# PCB-PAYLOAD-MIRRORED_FINAL.net
KiCad netlist of a schematic drawn in EAGLE
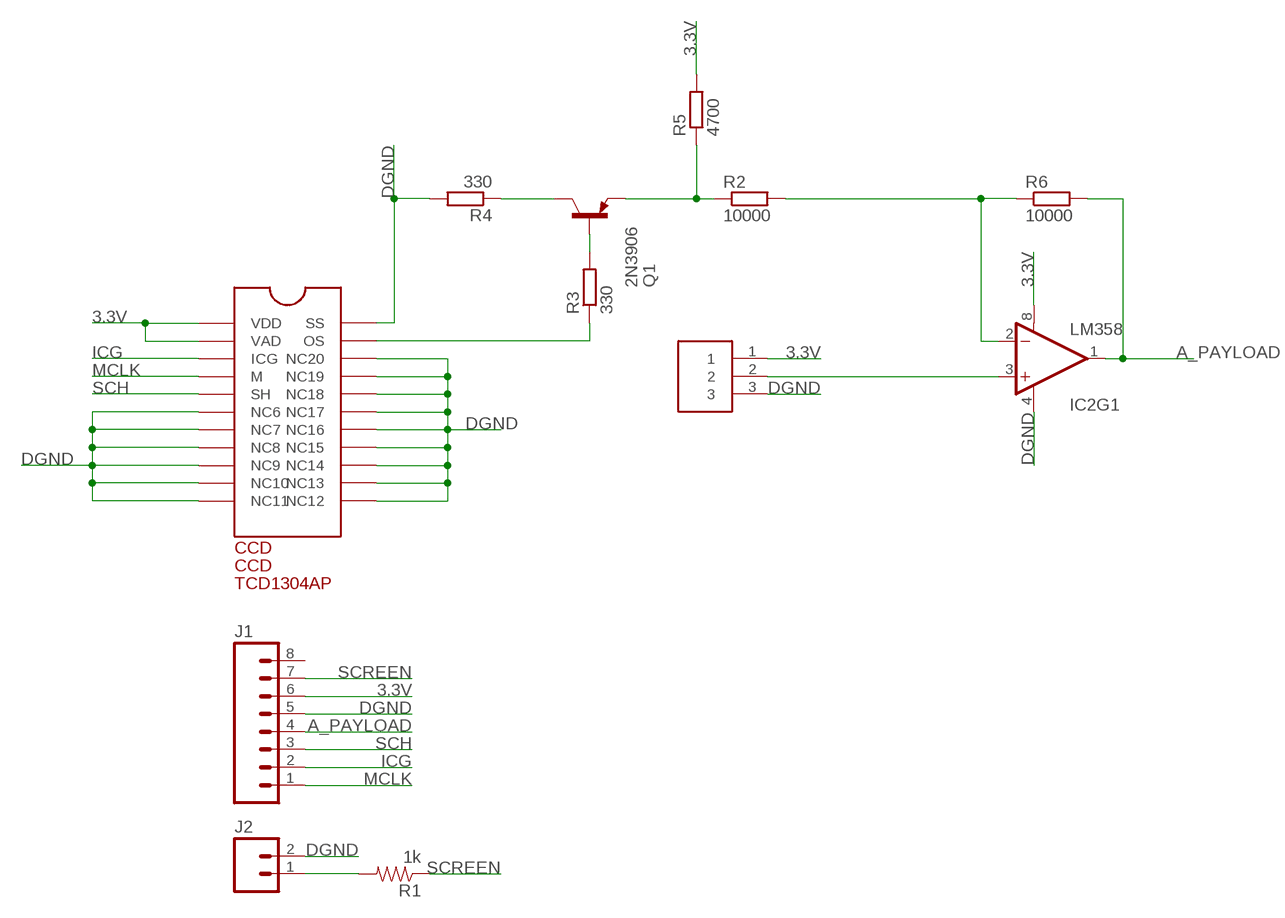
[diagram p0: schematic, sheet 1]

(export (version "E")
  (design (tool "Eeschema 10.0.6"))
  (components
    (comp (ref "CCD")
      (value "CCD")
      (footprint "eagle-import:CCD")
      (libsource (lib "eagle-import") (part "CCD"))
    )
    (comp (ref "IC2")
      (value "LM358")
      (footprint "eagle-import:DIP08")
      (libsource (lib "eagle-import") (part "LM358"))
    )
    (comp (ref "J1")
      (value "M08")
      (footprint "eagle-import:1X08_ROUND")
      (libsource (lib "eagle-import") (part "M08"))
    )
    (comp (ref "J2")
      (value "M02PTH")
      (footprint "eagle-import:1X02")
      (libsource (lib "eagle-import") (part "M02PTH"))
    )
    (comp (ref "Q1")
      (value "2N3906")
      (footprint "eagle-import:TO92")
      (libsource (lib "eagle-import") (part "2N3906"))
    )
    (comp (ref "R1")
      (value "1k")
      (footprint "eagle-import:AXIAL-0.3")
      (libsource (lib "eagle-import") (part "1KOHM-1/4W-5%(PTH)"))
    )
    (comp (ref "R2")
      (value "10000")
      (footprint "eagle-import:0204_5")
      (libsource (lib "eagle-import") (part "R-EU_0204/5"))
    )
    (comp (ref "R3")
      (value "330")
      (footprint "eagle-import:0204_5")
      (libsource (lib "eagle-import") (part "R-EU_0204/5"))
    )
    (comp (ref "R4")
      (value "330")
      (footprint "eagle-import:0204_5")
      (libsource (lib "eagle-import") (part "R-EU_0204/5"))
    )
    (comp (ref "R5")
      (value "4700")
      (footprint "eagle-import:0204_5")
      (libsource (lib "eagle-import") (part "R-EU_0204/5"))
    )
    (comp (ref "R6")
      (value "10000")
      (footprint "eagle-import:0204_5")
      (libsource (lib "eagle-import") (part "R-EU_0204/5"))
    )
    (comp (ref "U$2")
      (value "TRIMPOT_DEVICE")
      (footprint "eagle-import:TRIM_POT_PACKAGE")
      (libsource (lib "eagle-import") (part "TRIMPOT_DEVICE"))
    )
  )
  (nets
    (net (code "1") (name "/3.3V") (class "Default")
      (node (ref "CCD") (pin "VAD") (pinfunction "VAD_VAD") (pintype "bidirectional"))
      (node (ref "CCD") (pin "VDD") (pinfunction "VDD_VDD") (pintype "bidirectional"))
      (node (ref "IC2") (pin "8") (pinfunction "V+_8") (pintype "power_in"))
      (node (ref "J1") (pin "6") (pinfunction "6_6") (pintype "passive"))
      (node (ref "R5") (pin "2") (pinfunction "2_2") (pintype "passive"))
      (node (ref "U$2") (pin "1") (pinfunction "1_1") (pintype "bidirectional"))
    )
    (net (code "2") (name "/A_PAYLOAD") (class "Default")
      (node (ref "IC2") (pin "1") (pinfunction "OUT_1") (pintype "output"))
      (node (ref "J1") (pin "4") (pinfunction "4_4") (pintype "passive"))
      (node (ref "R6") (pin "2") (pinfunction "2_2") (pintype "passive"))
    )
    (net (code "3") (name "/DGND") (class "Default")
      (node (ref "CCD") (pin "NC10") (pinfunction "NC10_NC10") (pintype "bidirectional"))
      (node (ref "CCD") (pin "NC11") (pinfunction "NC11_NC11") (pintype "bidirectional"))
      (node (ref "CCD") (pin "NC12") (pinfunction "NC12_NC12") (pintype "bidirectional"))
      (node (ref "CCD") (pin "NC13") (pinfunction "NC13_NC13") (pintype "bidirectional"))
      (node (ref "CCD") (pin "NC14") (pinfunction "NC14_NC14") (pintype "bidirectional"))
      (node (ref "CCD") (pin "NC15") (pinfunction "NC15_NC15") (pintype "bidirectional"))
      (node (ref "CCD") (pin "NC16") (pinfunction "NC16_NC16") (pintype "bidirectional"))
      (node (ref "CCD") (pin "NC17") (pinfunction "NC17_NC17") (pintype "bidirectional"))
      (node (ref "CCD") (pin "NC18") (pinfunction "NC18_NC18") (pintype "bidirectional"))
      (node (ref "CCD") (pin "NC19") (pinfunction "NC19_NC19") (pintype "bidirectional"))
      (node (ref "CCD") (pin "NC20") (pinfunction "NC20_NC20") (pintype "bidirectional"))
      (node (ref "CCD") (pin "NC6") (pinfunction "NC6_NC6") (pintype "bidirectional"))
      (node (ref "CCD") (pin "NC7") (pinfunction "NC7_NC7") (pintype "bidirectional"))
      (node (ref "CCD") (pin "NC8") (pinfunction "NC8_NC8") (pintype "bidirectional"))
      (node (ref "CCD") (pin "NC9") (pinfunction "NC9_NC9") (pintype "bidirectional"))
      (node (ref "CCD") (pin "SS") (pinfunction "SS_SS") (pintype "bidirectional"))
      (node (ref "IC2") (pin "4") (pinfunction "V-_4") (pintype "power_in"))
      (node (ref "J1") (pin "5") (pinfunction "5_5") (pintype "passive"))
      (node (ref "J2") (pin "2") (pinfunction "2_2") (pintype "passive"))
      (node (ref "R4") (pin "2") (pinfunction "2_2") (pintype "passive"))
      (node (ref "U$2") (pin "3") (pinfunction "3_3") (pintype "bidirectional"))
    )
    (net (code "4") (name "/ICG") (class "Default")
      (node (ref "CCD") (pin "ICG") (pinfunction "ICG_ICG") (pintype "bidirectional"))
      (node (ref "J1") (pin "2") (pinfunction "2_2") (pintype "passive"))
    )
    (net (code "5") (name "/MCLK") (class "Default")
      (node (ref "CCD") (pin "M") (pinfunction "M_M") (pintype "bidirectional"))
      (node (ref "J1") (pin "1") (pinfunction "1_1") (pintype "passive"))
    )
    (net (code "6") (name "/SCH") (class "Default")
      (node (ref "CCD") (pin "SH") (pinfunction "SH_SH") (pintype "bidirectional"))
      (node (ref "J1") (pin "3") (pinfunction "3_3") (pintype "passive"))
    )
    (net (code "7") (name "/SCREEN") (class "Default")
      (node (ref "J1") (pin "7") (pinfunction "7_7") (pintype "passive"))
      (node (ref "R1") (pin "P$1") (pinfunction "1_P$1") (pintype "passive"))
    )
    (net (code "8") (name "Net-(CCD-PadOS)") (class "Default")
      (node (ref "CCD") (pin "OS") (pinfunction "OS_OS") (pintype "bidirectional"))
      (node (ref "R3") (pin "1") (pinfunction "1_1") (pintype "passive"))
    )
    (net (code "9") (name "Net-(IC2A-+IN)") (class "Default")
      (node (ref "IC2") (pin "3") (pinfunction "+IN_3") (pintype "input"))
      (node (ref "U$2") (pin "2") (pinfunction "2_2") (pintype "bidirectional"))
    )
    (net (code "10") (name "Net-(IC2A--IN)") (class "Default")
      (node (ref "IC2") (pin "2") (pinfunction "-IN_2") (pintype "input"))
      (node (ref "R2") (pin "2") (pinfunction "2_2") (pintype "passive"))
      (node (ref "R6") (pin "1") (pinfunction "1_1") (pintype "passive"))
    )
    (net (code "11") (name "Net-(Q1-B)") (class "Default")
      (node (ref "Q1") (pin "2") (pinfunction "B_2") (pintype "passive"))
      (node (ref "R3") (pin "2") (pinfunction "2_2") (pintype "passive"))
    )
    (net (code "12") (name "Net-(Q1-C)") (class "Default")
      (node (ref "Q1") (pin "1") (pinfunction "C_1") (pintype "passive"))
      (node (ref "R4") (pin "1") (pinfunction "1_1") (pintype "passive"))
    )
    (net (code "13") (name "Net-(Q1-E)") (class "Default")
      (node (ref "Q1") (pin "3") (pinfunction "E_3") (pintype "passive"))
      (node (ref "R2") (pin "1") (pinfunction "1_1") (pintype "passive"))
      (node (ref "R5") (pin "1") (pinfunction "1_1") (pintype "passive"))
    )
    (net (code "14") (name "Net-(R1-2)") (class "Default")
      (node (ref "J2") (pin "1") (pinfunction "1_1") (pintype "passive"))
      (node (ref "R1") (pin "P$2") (pinfunction "2_P$2") (pintype "passive"))
    )
    (net (code "15") (name "unconnected-(J1-Pad8)") (class "Default")
      (node (ref "J1") (pin "8") (pinfunction "8_8") (pintype "passive"))
    )
  )
)
